# SparkFun_Thing_Plus_NINA-B306.net
KiCad netlist of a schematic drawn in EAGLE
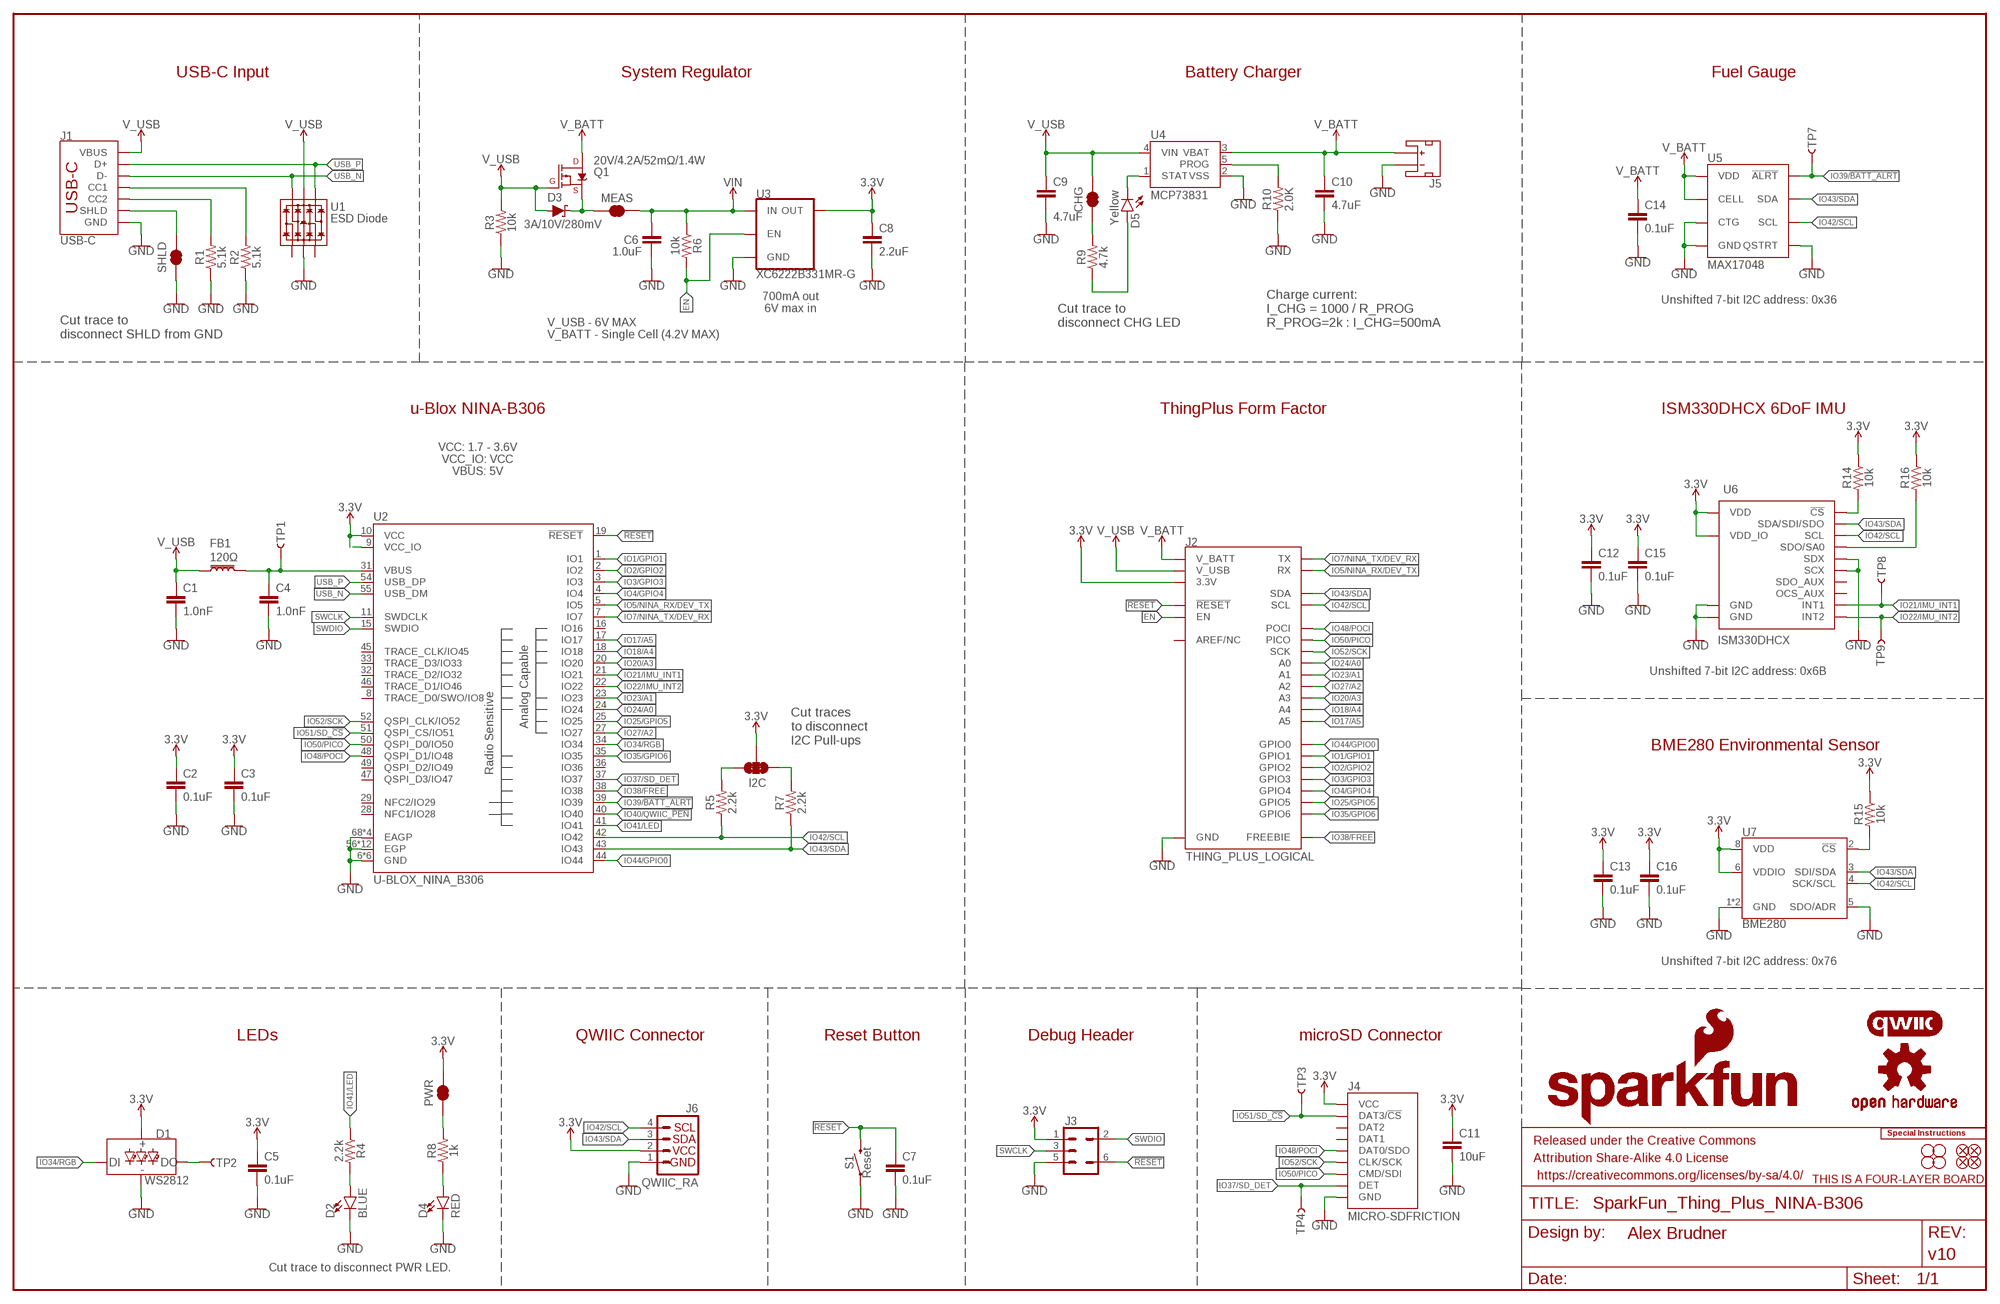
[diagram p0: schematic, sheet 1]

(export (version "E")
  (design (tool "Eeschema 10.0.6"))
  (components
    (comp (ref "C1")
      (value "1.0nF")
      (footprint "eagle-import:0402-TIGHT")
      (libsource (lib "eagle-import") (part "1.0NF/1000PF-0402_TIGHT-50V-10%"))
    )
    (comp (ref "C2")
      (value "0.1uF")
      (footprint "eagle-import:0402-TIGHT")
      (libsource (lib "eagle-import") (part "0.1UF-0402T-6.3V-10%-X7R"))
    )
    (comp (ref "C3")
      (value "0.1uF")
      (footprint "eagle-import:0402-TIGHT")
      (libsource (lib "eagle-import") (part "0.1UF-0402T-6.3V-10%-X7R"))
    )
    (comp (ref "C4")
      (value "1.0nF")
      (footprint "eagle-import:0402-TIGHT")
      (libsource (lib "eagle-import") (part "1.0NF/1000PF-0402_TIGHT-50V-10%"))
    )
    (comp (ref "C5")
      (value "0.1uF")
      (footprint "eagle-import:0402-TIGHT")
      (libsource (lib "eagle-import") (part "0.1UF-0402T-6.3V-10%-X7R"))
    )
    (comp (ref "C6")
      (value "1.0uF")
      (footprint "eagle-import:0402-TIGHT")
      (libsource (lib "eagle-import") (part "1.0UF-0402T-16V-10%"))
    )
    (comp (ref "C7")
      (value "0.1uF")
      (footprint "eagle-import:0402-TIGHT")
      (libsource (lib "eagle-import") (part "0.1UF-0402T-10V-10%-X7R"))
    )
    (comp (ref "C8")
      (value "2.2uF")
      (footprint "eagle-import:0402-TIGHT")
      (libsource (lib "eagle-import") (part "2.2UF-0402_TIGHT-10V-10%-X5R"))
    )
    (comp (ref "C9")
      (value "4.7uF")
      (footprint "eagle-import:0402-TIGHT")
      (libsource (lib "eagle-import") (part "4.7UF-0402_TIGHT-6.3V-20%-X5R"))
    )
    (comp (ref "C10")
      (value "4.7uF")
      (footprint "eagle-import:0402-TIGHT")
      (libsource (lib "eagle-import") (part "4.7UF-0402_TIGHT-6.3V-20%-X5R"))
    )
    (comp (ref "C11")
      (value "10uF")
      (footprint "eagle-import:0402-TIGHT")
      (libsource (lib "eagle-import") (part "10UF-0402T-6.3V-20%"))
    )
    (comp (ref "C12")
      (value "0.1uF")
      (footprint "eagle-import:0402-TIGHT")
      (libsource (lib "eagle-import") (part "0.1UF-0402T-6.3V-10%-X7R"))
    )
    (comp (ref "C13")
      (value "0.1uF")
      (footprint "eagle-import:0402-TIGHT")
      (libsource (lib "eagle-import") (part "0.1UF-0402T-6.3V-10%-X7R"))
    )
    (comp (ref "C14")
      (value "0.1uF")
      (footprint "eagle-import:0402-TIGHT")
      (libsource (lib "eagle-import") (part "0.1UF-0402T-10V-10%-X7R"))
    )
    (comp (ref "C15")
      (value "0.1uF")
      (footprint "eagle-import:0402-TIGHT")
      (libsource (lib "eagle-import") (part "0.1UF-0402T-6.3V-10%-X7R"))
    )
    (comp (ref "C16")
      (value "0.1uF")
      (footprint "eagle-import:0402-TIGHT")
      (libsource (lib "eagle-import") (part "0.1UF-0402T-6.3V-10%-X7R"))
    )
    (comp (ref "CHG")
      (value "JUMPER-SMT_2_NC_TRACE_SILK")
      (footprint "eagle-import:SMT-JUMPER_2_NC_TRACE_SILK")
      (libsource (lib "eagle-import") (part "JUMPER-SMT_2_NC_TRACE_SILK"))
    )
    (comp (ref "D1")
      (value "WS2812")
      (footprint "eagle-import:WS2812-2020")
      (libsource (lib "eagle-import") (part "WS2812_2020"))
    )
    (comp (ref "D2")
      (value "BLUE")
      (footprint "eagle-import:LED-0603")
      (libsource (lib "eagle-import") (part "LED-BLUE0603"))
    )
    (comp (ref "D3")
      (value "3A/10V/280mV")
      (footprint "eagle-import:SOD-323")
      (libsource (lib "eagle-import") (part "DIODE-SCHOTTKY-BAT60A"))
    )
    (comp (ref "D4")
      (value "RED")
      (footprint "eagle-import:LED-0603")
      (libsource (lib "eagle-import") (part "LED-RED0603"))
    )
    (comp (ref "D5")
      (value "Yellow")
      (footprint "eagle-import:LED-0603")
      (libsource (lib "eagle-import") (part "LED-YELLOW0603"))
    )
    (comp (ref "FB1")
      (value "120Ω")
      (footprint "eagle-import:0402")
      (fields (field (name "MFG_PART") "BLM15HB121SN1D"))
      (libsource (lib "eagle-import") (part "FERRITE_BEAD-120_OHM-0402"))
    )
    (comp (ref "FD1")
      (value "FIDUCIALUFIDUCIAL")
      (footprint "eagle-import:FIDUCIAL-MICRO")
      (libsource (lib "eagle-import") (part "FIDUCIALUFIDUCIAL"))
    )
    (comp (ref "FD2")
      (value "FIDUCIALUFIDUCIAL")
      (footprint "eagle-import:FIDUCIAL-MICRO")
      (libsource (lib "eagle-import") (part "FIDUCIALUFIDUCIAL"))
    )
    (comp (ref "FD3")
      (value "FIDUCIALUFIDUCIAL")
      (footprint "eagle-import:FIDUCIAL-MICRO")
      (libsource (lib "eagle-import") (part "FIDUCIALUFIDUCIAL"))
    )
    (comp (ref "FD4")
      (value "FIDUCIALUFIDUCIAL")
      (footprint "eagle-import:FIDUCIAL-MICRO")
      (libsource (lib "eagle-import") (part "FIDUCIALUFIDUCIAL"))
    )
    (comp (ref "FRAME1")
      (value "FRAME-LEDGER")
      (footprint "eagle-import:CREATIVE_COMMONS")
      (fields (field (name "DESIGNER") "Alex Brudner") (field (name "REV") "v10"))
      (libsource (lib "eagle-import") (part "FRAME-LEDGER"))
    )
    (comp (ref "H1")
      (value "STAND-OFFTIGHT")
      (footprint "eagle-import:STAND-OFF-TIGHT")
      (libsource (lib "eagle-import") (part "STAND-OFFTIGHT"))
    )
    (comp (ref "H2")
      (value "STAND-OFFTIGHT")
      (footprint "eagle-import:STAND-OFF-TIGHT")
      (libsource (lib "eagle-import") (part "STAND-OFFTIGHT"))
    )
    (comp (ref "H3")
      (value "STAND-OFFTIGHT")
      (footprint "eagle-import:STAND-OFF-TIGHT")
      (libsource (lib "eagle-import") (part "STAND-OFFTIGHT"))
    )
    (comp (ref "H4")
      (value "STAND-OFFTIGHT")
      (footprint "eagle-import:STAND-OFF-TIGHT")
      (libsource (lib "eagle-import") (part "STAND-OFFTIGHT"))
    )
    (comp (ref "I2C")
      (value "JUMPER-SMT_3_2-NC_TRACE_SILK")
      (footprint "eagle-import:SMT-JUMPER_3_2-NC_TRACE_SILK")
      (libsource (lib "eagle-import") (part "JUMPER-SMT_3_2-NC_TRACE_SILK"))
    )
    (comp (ref "J1")
      (value "USB-C")
      (footprint "eagle-import:USB-C-16P-4LAYER-ISOLATED")
      (libsource (lib "eagle-import") (part "USB_C_4-LAYER-ISOLATED"))
    )
    (comp (ref "J2")
      (value "THING_PLUS_LOGICAL")
      (footprint "eagle-import:THING_PLUS")
      (libsource (lib "eagle-import") (part "THING_PLUS_LOGICAL"))
    )
    (comp (ref "J3")
      (value "CONN_03X2_NO4")
      (footprint "eagle-import:PAD_05_03X2_TP_NO4")
      (libsource (lib "eagle-import") (part "CONN_03X2_NO4"))
    )
    (comp (ref "J4")
      (value "MICRO-SDFRICTION")
      (footprint "eagle-import:MICROSD_TINY")
      (libsource (lib "eagle-import") (part "MICRO-SDFRICTION"))
    )
    (comp (ref "J5")
      (value "JST_2MM_MALE")
      (footprint "eagle-import:JST-2-SMD")
      (libsource (lib "eagle-import") (part "JST_2MM_MALE"))
    )
    (comp (ref "J6")
      (value "QWIIC_RA")
      (footprint "eagle-import:JST04_1MM_RA")
      (libsource (lib "eagle-import") (part "QWIIC_CONNECTORJS-1MM"))
    )
    (comp (ref "LOGO1")
      (value "SFE_LOGO_NAME_FLAME.1_INCH")
      (footprint "eagle-import:SFE_LOGO_NAME_FLAME_.1")
      (libsource (lib "eagle-import") (part "SFE_LOGO_NAME_FLAME.1_INCH"))
    )
    (comp (ref "LOGO2")
      (value "FOUR_LAYER_WARNING")
      (footprint "eagle-import:FOUR_LAYER_WARNING")
      (libsource (lib "eagle-import") (part "FOUR_LAYER_WARNING"))
    )
    (comp (ref "LOGO3")
      (value "SPECIAL_INSTRUCTIONS-ORDERING")
      (footprint "eagle-import:ORDERING_INSTRUCTIONS")
      (libsource (lib "eagle-import") (part "SPECIAL_INSTRUCTIONS-ORDERING"))
    )
    (comp (ref "LOGO4")
      (value "QWIIC_LOGO_4MM")
      (footprint "eagle-import:QWIIC_4MM")
      (libsource (lib "eagle-import") (part "QWIIC_LOGO_4MM"))
    )
    (comp (ref "LOGO5")
      (value "OSHW-LOGOMINI")
      (footprint "eagle-import:OSHW-LOGO-MINI")
      (libsource (lib "eagle-import") (part "OSHW-LOGOMINI"))
    )
    (comp (ref "MEAS")
      (value "JUMPER-COMBO_2_NC_TRACE")
      (footprint "eagle-import:COMBO-JUMPER_2_NC_TRACE")
      (libsource (lib "eagle-import") (part "JUMPER-COMBO_2_NC_TRACE"))
    )
    (comp (ref "PWR")
      (value "JUMPER-SMT_2_NC_TRACE_SILK")
      (footprint "eagle-import:SMT-JUMPER_2_NC_TRACE_SILK")
      (libsource (lib "eagle-import") (part "JUMPER-SMT_2_NC_TRACE_SILK"))
    )
    (comp (ref "Q1")
      (value "20V/4.2A/52mΩ/1.4W")
      (footprint "eagle-import:SOT23-3")
      (libsource (lib "eagle-import") (part "MOSFET_PCH-DMG2305UX-7"))
    )
    (comp (ref "R1")
      (value "5.1k")
      (footprint "eagle-import:0402-TIGHT")
      (libsource (lib "eagle-import") (part "5.1KOHM-0402T-1/16W-1%"))
    )
    (comp (ref "R2")
      (value "5.1k")
      (footprint "eagle-import:0402-TIGHT")
      (libsource (lib "eagle-import") (part "5.1KOHM-0402T-1/16W-1%"))
    )
    (comp (ref "R3")
      (value "10k")
      (footprint "eagle-import:0402-TIGHT")
      (libsource (lib "eagle-import") (part "10KOHM-0402T-1/16W-1%"))
    )
    (comp (ref "R4")
      (value "2.2k")
      (footprint "eagle-import:0402-TIGHT")
      (libsource (lib "eagle-import") (part "2.2KOHM-0402T-1/16W-1%"))
    )
    (comp (ref "R5")
      (value "2.2k")
      (footprint "eagle-import:0402-TIGHT")
      (libsource (lib "eagle-import") (part "2.2KOHM-0402T-1/16W-1%"))
    )
    (comp (ref "R6")
      (value "10k")
      (footprint "eagle-import:0402-TIGHT")
      (libsource (lib "eagle-import") (part "10KOHM-0402T-1/16W-1%"))
    )
    (comp (ref "R7")
      (value "2.2k")
      (footprint "eagle-import:0402-TIGHT")
      (libsource (lib "eagle-import") (part "2.2KOHM-0402T-1/16W-1%"))
    )
    (comp (ref "R8")
      (value "1k")
      (footprint "eagle-import:0402-TIGHT")
      (libsource (lib "eagle-import") (part "1KOHM-0402T-1/16W-1%"))
    )
    (comp (ref "R9")
      (value "4.7k")
      (footprint "eagle-import:0402-TIGHT")
      (libsource (lib "eagle-import") (part "4.7KOHM-0402T-1/16W-1%"))
    )
    (comp (ref "R10")
      (value "2.0K")
      (footprint "eagle-import:0402-TIGHT")
      (libsource (lib "eagle-import") (part "2.0KOHM-0402T-1/16W-1%"))
    )
    (comp (ref "R14")
      (value "10k")
      (footprint "eagle-import:0402-TIGHT")
      (libsource (lib "eagle-import") (part "10KOHM-0402T-1/16W-1%"))
    )
    (comp (ref "R15")
      (value "10k")
      (footprint "eagle-import:0402-TIGHT")
      (libsource (lib "eagle-import") (part "10KOHM-0402T-1/16W-1%"))
    )
    (comp (ref "R16")
      (value "10k")
      (footprint "eagle-import:0402-TIGHT")
      (libsource (lib "eagle-import") (part "10KOHM-0402T-1/16W-1%"))
    )
    (comp (ref "S1")
      (value "Reset")
      (footprint "eagle-import:TACTILE_SWITCH_SMD_4.6X2.8MM")
      (libsource (lib "eagle-import") (part "MOMENTARY-SWITCH-SPST-SMD-4.6X2.8MM"))
    )
    (comp (ref "SHLD")
      (value "JUMPER-SMT_2_NC_TRACE_SILK")
      (footprint "eagle-import:SMT-JUMPER_2_NC_TRACE_SILK")
      (libsource (lib "eagle-import") (part "JUMPER-SMT_2_NC_TRACE_SILK"))
    )
    (comp (ref "TP1")
      (value "TEST-POINT3X5")
      (footprint "eagle-import:PAD.03X.05")
      (libsource (lib "eagle-import") (part "TEST-POINT3X5"))
    )
    (comp (ref "TP2")
      (value "TEST-POINT3X5")
      (footprint "eagle-import:PAD.03X.05")
      (libsource (lib "eagle-import") (part "TEST-POINT3X5"))
    )
    (comp (ref "TP3")
      (value "TEST-POINT3X5")
      (footprint "eagle-import:PAD.03X.05")
      (libsource (lib "eagle-import") (part "TEST-POINT3X5"))
    )
    (comp (ref "TP4")
      (value "TEST-POINT3X5")
      (footprint "eagle-import:PAD.03X.05")
      (libsource (lib "eagle-import") (part "TEST-POINT3X5"))
    )
    (comp (ref "TP7")
      (value "TEST-POINT3X5")
      (footprint "eagle-import:PAD.03X.05")
      (libsource (lib "eagle-import") (part "TEST-POINT3X5"))
    )
    (comp (ref "TP8")
      (value "TEST-POINT3X5")
      (footprint "eagle-import:PAD.03X.05")
      (libsource (lib "eagle-import") (part "TEST-POINT3X5"))
    )
    (comp (ref "TP9")
      (value "TEST-POINT3X5")
      (footprint "eagle-import:PAD.03X.05")
      (libsource (lib "eagle-import") (part "TEST-POINT3X5"))
    )
    (comp (ref "U1")
      (value "ESD Diode")
      (footprint "eagle-import:SOT-23-6")
      (libsource (lib "eagle-import") (part "TVS_DIODE_ARRAY_DT1042-04SO-7"))
    )
    (comp (ref "U2")
      (value "U-BLOX_NINA_B306")
      (footprint "eagle-import:NINA_B306")
      (libsource (lib "eagle-import") (part "U-BLOX_NINA_B306"))
    )
    (comp (ref "U3")
      (value "XC6222B331MR-G")
      (footprint "eagle-import:SOT23-5")
      (libsource (lib "eagle-import") (part "XC6222B331MR-G"))
    )
    (comp (ref "U4")
      (value "MCP73831")
      (footprint "eagle-import:SOT23-5")
      (libsource (lib "eagle-import") (part "MCP73831"))
    )
    (comp (ref "U5")
      (value "MAX17048")
      (footprint "eagle-import:DFN-8")
      (libsource (lib "eagle-import") (part "MAX17048DFN8"))
    )
    (comp (ref "U6")
      (value "ISM330DHCX")
      (footprint "eagle-import:LGA-14L")
      (libsource (lib "eagle-import") (part "ISM330DHCX"))
    )
    (comp (ref "U7")
      (value "BME280")
      (footprint "eagle-import:LGA-8-2.5X2.5")
      (libsource (lib "eagle-import") (part "BME280"))
    )
  )
  (nets
    (net (code "1") (name "/IO39{slash}~{BATT_ALRT}") (class "Default")
      (node (ref "TP7") (pin "1") (pinfunction "1_1") (pintype "bidirectional"))
      (node (ref "U2") (pin "39") (pinfunction "IO39_39") (pintype "bidirectional"))
      (node (ref "U5") (pin "5") (pinfunction "~{ALRT}_5") (pintype "bidirectional"))
    )
    (net (code "2") (name "/IO40{slash}QWIIC_~{PEN}") (class "Default")
      (node (ref "U2") (pin "40") (pinfunction "IO40_40") (pintype "bidirectional"))
    )
    (net (code "3") (name "/IO51{slash}SD_~{CS}") (class "Default")
      (node (ref "J4") (pin "2") (pinfunction "DAT3/~{CS}_2") (pintype "bidirectional"))
      (node (ref "TP3") (pin "1") (pinfunction "1_1") (pintype "bidirectional"))
      (node (ref "U2") (pin "51") (pinfunction "QSPI_CS/IO51_51") (pintype "bidirectional"))
    )
    (net (code "4") (name "/~{RESET}") (class "Default")
      (node (ref "C7") (pin "1") (pinfunction "1_1") (pintype "passive"))
      (node (ref "J2") (pin "28") (pinfunction "~{RESET}_28") (pintype "bidirectional"))
      (node (ref "J3") (pin "6") (pinfunction "6_6") (pintype "bidirectional"))
      (node (ref "S1") (pin "3") (pinfunction "2_3") (pintype "passive"))
      (node (ref "S1") (pin "4") (pinfunction "2_4") (pintype "passive"))
      (node (ref "U2") (pin "19") (pinfunction "~{RESET}_19") (pintype "input"))
    )
    (net (code "5") (name "3.3V") (class "Default")
      (node (ref "C11") (pin "1") (pinfunction "1_1") (pintype "passive"))
      (node (ref "C12") (pin "1") (pinfunction "1_1") (pintype "passive"))
      (node (ref "C13") (pin "1") (pinfunction "1_1") (pintype "passive"))
      (node (ref "C15") (pin "1") (pinfunction "1_1") (pintype "passive"))
      (node (ref "C16") (pin "1") (pinfunction "1_1") (pintype "passive"))
      (node (ref "C2") (pin "1") (pinfunction "1_1") (pintype "passive"))
      (node (ref "C3") (pin "1") (pinfunction "1_1") (pintype "passive"))
      (node (ref "C5") (pin "1") (pinfunction "1_1") (pintype "passive"))
      (node (ref "C8") (pin "1") (pinfunction "1_1") (pintype "passive"))
      (node (ref "D1") (pin "VCC") (pinfunction "VCC_VCC") (pintype "bidirectional"))
      (node (ref "I2C") (pin "2") (pinfunction "2_2") (pintype "passive"))
      (node (ref "J2") (pin "27") (pinfunction "3.3V_27") (pintype "bidirectional"))
      (node (ref "J3") (pin "1") (pinfunction "1_1") (pintype "bidirectional"))
      (node (ref "J4") (pin "4") (pinfunction "VCC_4") (pintype "bidirectional"))
      (node (ref "J6") (pin "2") (pinfunction "2_2") (pintype "power_in"))
      (node (ref "PWR") (pin "2") (pinfunction "2_2") (pintype "passive"))
      (node (ref "R14") (pin "1") (pinfunction "1_1") (pintype "passive"))
      (node (ref "R15") (pin "1") (pinfunction "1_1") (pintype "passive"))
      (node (ref "R16") (pin "1") (pinfunction "1_1") (pintype "passive"))
      (node (ref "U2") (pin "10") (pinfunction "VCC_10") (pintype "power_in"))
      (node (ref "U2") (pin "9") (pinfunction "VCC_IO_9") (pintype "power_in"))
      (node (ref "U3") (pin "5") (pinfunction "OUT_5") (pintype "passive"))
      (node (ref "U6") (pin "P5") (pinfunction "VDD_IO_P5") (pintype "power_in"))
      (node (ref "U6") (pin "P8") (pinfunction "VDD_P8") (pintype "power_in"))
      (node (ref "U7") (pin "6") (pinfunction "VDDIO_6") (pintype "bidirectional"))
      (node (ref "U7") (pin "8") (pinfunction "VDD_8") (pintype "bidirectional"))
    )
    (net (code "6") (name "EN") (class "Default")
      (node (ref "J2") (pin "11") (pinfunction "EN_11") (pintype "bidirectional"))
      (node (ref "R6") (pin "2") (pinfunction "2_2") (pintype "passive"))
      (node (ref "U3") (pin "3") (pinfunction "EN_3") (pintype "input"))
    )
    (net (code "7") (name "GND") (class "Default")
      (node (ref "C1") (pin "2") (pinfunction "2_2") (pintype "passive"))
      (node (ref "C10") (pin "2") (pinfunction "2_2") (pintype "passive"))
      (node (ref "C11") (pin "2") (pinfunction "2_2") (pintype "passive"))
      (node (ref "C12") (pin "2") (pinfunction "2_2") (pintype "passive"))
      (node (ref "C13") (pin "2") (pinfunction "2_2") (pintype "passive"))
      (node (ref "C14") (pin "2") (pinfunction "2_2") (pintype "passive"))
      (node (ref "C15") (pin "2") (pinfunction "2_2") (pintype "passive"))
      (node (ref "C16") (pin "2") (pinfunction "2_2") (pintype "passive"))
      (node (ref "C2") (pin "2") (pinfunction "2_2") (pintype "passive"))
      (node (ref "C3") (pin "2") (pinfunction "2_2") (pintype "passive"))
      (node (ref "C4") (pin "2") (pinfunction "2_2") (pintype "passive"))
      (node (ref "C5") (pin "2") (pinfunction "2_2") (pintype "passive"))
      (node (ref "C6") (pin "2") (pinfunction "2_2") (pintype "passive"))
      (node (ref "C7") (pin "2") (pinfunction "2_2") (pintype "passive"))
      (node (ref "C8") (pin "2") (pinfunction "2_2") (pintype "passive"))
      (node (ref "C9") (pin "2") (pinfunction "2_2") (pintype "passive"))
      (node (ref "D1") (pin "GND") (pinfunction "GND_GND") (pintype "bidirectional"))
      (node (ref "D2") (pin "C") (pinfunction "C_C") (pintype "passive"))
      (node (ref "D4") (pin "C") (pinfunction "C_C") (pintype "passive"))
      (node (ref "J1") (pin "GND") (pinfunction "GND_GND") (pintype "bidirectional"))
      (node (ref "J1") (pin "GND2") (pinfunction "GND_GND2") (pintype "bidirectional"))
      (node (ref "J2") (pin "25") (pinfunction "GND_25") (pintype "bidirectional"))
      (node (ref "J3") (pin "5") (pinfunction "5_5") (pintype "bidirectional"))
      (node (ref "J4") (pin "6") (pinfunction "GND_6") (pintype "bidirectional"))
      (node (ref "J4") (pin "GND1") (pinfunction "GND_GND1") (pintype "bidirectional"))
      (node (ref "J4") (pin "GND2") (pinfunction "GND_GND2") (pintype "bidirectional"))
      (node (ref "J4") (pin "GND3") (pinfunction "GND_GND3") (pintype "bidirectional"))
      (node (ref "J4") (pin "GND4") (pinfunction "GND_GND4") (pintype "bidirectional"))
      (node (ref "J4") (pin "GND5") (pinfunction "GND_GND5") (pintype "bidirectional"))
      (node (ref "J4") (pin "GND6") (pinfunction "GND_GND6") (pintype "bidirectional"))
      (node (ref "J5") (pin "1") (pinfunction "-_1") (pintype "bidirectional"))
      (node (ref "J6") (pin "1") (pinfunction "1_1") (pintype "power_in"))
      (node (ref "R1") (pin "1") (pinfunction "1_1") (pintype "passive"))
      (node (ref "R10") (pin "1") (pinfunction "1_1") (pintype "passive"))
      (node (ref "R2") (pin "1") (pinfunction "1_1") (pintype "passive"))
      (node (ref "R3") (pin "1") (pinfunction "1_1") (pintype "passive"))
      (node (ref "S1") (pin "1") (pinfunction "1_1") (pintype "passive"))
      (node (ref "S1") (pin "2") (pinfunction "1_2") (pintype "passive"))
      (node (ref "SHLD") (pin "1") (pinfunction "1_1") (pintype "passive"))
      (node (ref "U1") (pin "2") (pinfunction "VSS_2") (pintype "bidirectional"))
      (node (ref "U2") (pin "12") (pinfunction "GND_12") (pintype "power_in"))
      (node (ref "U2") (pin "14") (pinfunction "GND_14") (pintype "power_in"))
      (node (ref "U2") (pin "26") (pinfunction "GND_26") (pintype "power_in"))
      (node (ref "U2") (pin "30") (pinfunction "GND_30") (pintype "power_in"))
      (node (ref "U2") (pin "53") (pinfunction "GND_53") (pintype "power_in"))
      (node (ref "U2") (pin "56") (pinfunction "EGP_56") (pintype "power_in"))
      (node (ref "U2") (pin "57") (pinfunction "EGP_57") (pintype "power_in"))
      (node (ref "U2") (pin "58") (pinfunction "EGP_58") (pintype "power_in"))
      (node (ref "U2") (pin "59") (pinfunction "EGP_59") (pintype "power_in"))
      (node (ref "U2") (pin "6") (pinfunction "GND_6") (pintype "power_in"))
      (node (ref "U2") (pin "60") (pinfunction "EGP_60") (pintype "power_in"))
      (node (ref "U2") (pin "61") (pinfunction "EGP_61") (pintype "power_in"))
      (node (ref "U2") (pin "62") (pinfunction "EGP_62") (pintype "power_in"))
      (node (ref "U2") (pin "63") (pinfunction "EGP_63") (pintype "power_in"))
      (node (ref "U2") (pin "64") (pinfunction "EGP_64") (pintype "power_in"))
      (node (ref "U2") (pin "65") (pinfunction "EGP_65") (pintype "power_in"))
      (node (ref "U2") (pin "66") (pinfunction "EGP_66") (pintype "power_in"))
      (node (ref "U2") (pin "67") (pinfunction "EGP_67") (pintype "power_in"))
      (node (ref "U2") (pin "68") (pinfunction "EAGP_68") (pintype "power_in"))
      (node (ref "U2") (pin "69") (pinfunction "EAGP_69") (pintype "power_in"))
      (node (ref "U2") (pin "70") (pinfunction "EAGP_70") (pintype "power_in"))
      (node (ref "U2") (pin "71") (pinfunction "EAGP_71") (pintype "power_in"))
      (node (ref "U3") (pin "2") (pinfunction "GND_2") (pintype "input"))
      (node (ref "U4") (pin "2") (pinfunction "VSS_2") (pintype "power_in"))
      (node (ref "U5") (pin "1") (pinfunction "CTG_1") (pintype "input"))
      (node (ref "U5") (pin "4") (pinfunction "GND_4") (pintype "bidirectional"))
      (node (ref "U5") (pin "6") (pinfunction "QSTRT_6") (pintype "bidirectional"))
      (node (ref "U5") (pin "9") (pinfunction "GND_9") (pintype "bidirectional"))
      (node (ref "U6") (pin "P2") (pinfunction "SDX_P2") (pintype "bidirectional"))
      (node (ref "U6") (pin "P3") (pinfunction "SCX_P3") (pintype "bidirectional"))
      (node (ref "U6") (pin "P6") (pinfunction "GND_P6") (pintype "power_in"))
      (node (ref "U6") (pin "P7") (pinfunction "GND_P7") (pintype "power_in"))
      (node (ref "U7") (pin "1") (pinfunction "GND_1") (pintype "bidirectional"))
      (node (ref "U7") (pin "5") (pinfunction "SDO/ADR_5") (pintype "bidirectional"))
      (node (ref "U7") (pin "7") (pinfunction "GND_7") (pintype "bidirectional"))
    )
    (net (code "8") (name "IO1{slash}GPIO1") (class "Default")
      (node (ref "J2") (pin "8") (pinfunction "GPIO1_8") (pintype "bidirectional"))
      (node (ref "U2") (pin "1") (pinfunction "IO1_1") (pintype "bidirectional"))
    )
    (net (code "9") (name "IO2{slash}GPIO2") (class "Default")
      (node (ref "J2") (pin "7") (pinfunction "GPIO2_7") (pintype "bidirectional"))
      (node (ref "U2") (pin "2") (pinfunction "IO2_2") (pintype "bidirectional"))
    )
    (net (code "10") (name "IO3{slash}GPIO3") (class "Default")
      (node (ref "J2") (pin "6") (pinfunction "GPIO3_6") (pintype "bidirectional"))
      (node (ref "U2") (pin "3") (pinfunction "IO3_3") (pintype "bidirectional"))
    )
    (net (code "11") (name "IO4{slash}GPIO4") (class "Default")
      (node (ref "J2") (pin "5") (pinfunction "GPIO4_5") (pintype "bidirectional"))
      (node (ref "U2") (pin "4") (pinfunction "IO4_4") (pintype "bidirectional"))
    )
    (net (code "12") (name "IO5{slash}NINA_RX{slash}DEV_TX") (class "Default")
      (node (ref "J2") (pin "15") (pinfunction "RX_15") (pintype "bidirectional"))
      (node (ref "U2") (pin "5") (pinfunction "IO5_5") (pintype "bidirectional"))
    )
    (net (code "13") (name "IO7{slash}NINA_TX{slash}DEV_RX") (class "Default")
      (node (ref "J2") (pin "14") (pinfunction "TX_14") (pintype "bidirectional"))
      (node (ref "U2") (pin "7") (pinfunction "IO7_7") (pintype "bidirectional"))
    )
    (net (code "14") (name "IO17{slash}A5") (class "Default")
      (node (ref "J2") (pin "19") (pinfunction "A5_19") (pintype "bidirectional"))
      (node (ref "U2") (pin "17") (pinfunction "IO17_17") (pintype "bidirectional"))
    )
    (net (code "15") (name "IO18{slash}A4") (class "Default")
      (node (ref "J2") (pin "20") (pinfunction "A4_20") (pintype "bidirectional"))
      (node (ref "U2") (pin "18") (pinfunction "IO18_18") (pintype "bidirectional"))
    )
    (net (code "16") (name "IO20{slash}A3") (class "Default")
      (node (ref "J2") (pin "21") (pinfunction "A3_21") (pintype "bidirectional"))
      (node (ref "U2") (pin "20") (pinfunction "IO20_20") (pintype "bidirectional"))
    )
    (net (code "17") (name "IO21{slash}IMU_INT1") (class "Default")
      (node (ref "TP8") (pin "1") (pinfunction "1_1") (pintype "bidirectional"))
      (node (ref "U2") (pin "21") (pinfunction "IO21_21") (pintype "bidirectional"))
      (node (ref "U6") (pin "P4") (pinfunction "INT1_P4") (pintype "bidirectional"))
    )
    (net (code "18") (name "IO22{slash}IMU_INT2") (class "Default")
      (node (ref "TP9") (pin "1") (pinfunction "1_1") (pintype "bidirectional"))
      (node (ref "U2") (pin "22") (pinfunction "IO22_22") (pintype "bidirectional"))
      (node (ref "U6") (pin "P9") (pinfunction "INT2_P9") (pintype "bidirectional"))
    )
    (net (code "19") (name "IO23{slash}A1") (class "Default")
      (node (ref "J2") (pin "23") (pinfunction "A1_23") (pintype "bidirectional"))
      (node (ref "U2") (pin "23") (pinfunction "IO23_23") (pintype "bidirectional"))
    )
    (net (code "20") (name "IO24{slash}A0") (class "Default")
      (node (ref "J2") (pin "24") (pinfunction "A0_24") (pintype "bidirectional"))
      (node (ref "U2") (pin "24") (pinfunction "IO24_24") (pintype "bidirectional"))
    )
    (net (code "21") (name "IO25{slash}GPIO5") (class "Default")
      (node (ref "J2") (pin "4") (pinfunction "GPIO5_4") (pintype "bidirectional"))
      (node (ref "U2") (pin "25") (pinfunction "IO25_25") (pintype "bidirectional"))
    )
    (net (code "22") (name "IO27{slash}A2") (class "Default")
      (node (ref "J2") (pin "22") (pinfunction "A2_22") (pintype "bidirectional"))
      (node (ref "U2") (pin "27") (pinfunction "IO27_27") (pintype "bidirectional"))
    )
    (net (code "23") (name "IO34{slash}RGB") (class "Default")
      (node (ref "D1") (pin "DI") (pinfunction "DI_DI") (pintype "bidirectional"))
      (node (ref "U2") (pin "34") (pinfunction "IO34_34") (pintype "bidirectional"))
    )
    (net (code "24") (name "IO35{slash}GPIO6") (class "Default")
      (node (ref "J2") (pin "3") (pinfunction "GPIO6_3") (pintype "bidirectional"))
      (node (ref "U2") (pin "35") (pinfunction "IO35_35") (pintype "bidirectional"))
    )
    (net (code "25") (name "IO37{slash}SD_DET") (class "Default")
      (node (ref "J4") (pin "9") (pinfunction "DET_9") (pintype "bidirectional"))
      (node (ref "TP4") (pin "1") (pinfunction "1_1") (pintype "bidirectional"))
      (node (ref "U2") (pin "37") (pinfunction "IO37_37") (pintype "bidirectional"))
    )
    (net (code "26") (name "IO38{slash}FREE") (class "Default")
      (node (ref "J2") (pin "13") (pinfunction "FREEBIE_13") (pintype "bidirectional"))
      (node (ref "U2") (pin "38") (pinfunction "IO38_38") (pintype "bidirectional"))
    )
    (net (code "27") (name "IO41{slash}LED") (class "Default")
      (node (ref "R4") (pin "1") (pinfunction "1_1") (pintype "passive"))
      (node (ref "U2") (pin "41") (pinfunction "IO41_41") (pintype "bidirectional"))
    )
    (net (code "28") (name "IO42{slash}SCL") (class "Default")
      (node (ref "J2") (pin "2") (pinfunction "SCL_2") (pintype "bidirectional"))
      (node (ref "J6") (pin "4") (pinfunction "4_4") (pintype "passive"))
      (node (ref "R5") (pin "1") (pinfunction "1_1") (pintype "passive"))
      (node (ref "U2") (pin "42") (pinfunction "IO42_42") (pintype "bidirectional"))
      (node (ref "U5") (pin "7") (pinfunction "SCL_7") (pintype "output"))
      (node (ref "U6") (pin "P13") (pinfunction "SCL_P13") (pintype "bidirectional"))
      (node (ref "U7") (pin "4") (pinfunction "SCK/SCL_4") (pintype "bidirectional"))
    )
    (net (code "29") (name "IO43{slash}SDA") (class "Default")
      (node (ref "J2") (pin "1") (pinfunction "SDA_1") (pintype "bidirectional"))
      (node (ref "J6") (pin "3") (pinfunction "3_3") (pintype "passive"))
      (node (ref "R7") (pin "1") (pinfunction "1_1") (pintype "passive"))
      (node (ref "U2") (pin "43") (pinfunction "IO43_43") (pintype "bidirectional"))
      (node (ref "U5") (pin "8") (pinfunction "SDA_8") (pintype "input"))
      (node (ref "U6") (pin "P14") (pinfunction "SDA/SDI/SDO_P14") (pintype "bidirectional"))
      (node (ref "U7") (pin "3") (pinfunction "SDI/SDA_3") (pintype "bidirectional"))
    )
    (net (code "30") (name "IO44{slash}GPIO0") (class "Default")
      (node (ref "J2") (pin "9") (pinfunction "GPIO0_9") (pintype "bidirectional"))
      (node (ref "U2") (pin "44") (pinfunction "IO44_44") (pintype "bidirectional"))
    )
    (net (code "31") (name "IO48{slash}POCI") (class "Default")
      (node (ref "J2") (pin "16") (pinfunction "POCI_16") (pintype "bidirectional"))
      (node (ref "J4") (pin "7") (pinfunction "DAT0/SDO_7") (pintype "bidirectional"))
      (node (ref "U2") (pin "48") (pinfunction "QSPI_D1/IO48_48") (pintype "bidirectional"))
    )
    (net (code "32") (name "IO50{slash}PICO") (class "Default")
      (node (ref "J2") (pin "17") (pinfunction "PICO_17") (pintype "bidirectional"))
      (node (ref "J4") (pin "3") (pinfunction "CMD/SDI_3") (pintype "bidirectional"))
      (node (ref "U2") (pin "50") (pinfunction "QSPI_D0/IO50_50") (pintype "bidirectional"))
    )
    (net (code "33") (name "IO52{slash}SCK") (class "Default")
      (node (ref "J2") (pin "18") (pinfunction "SCK_18") (pintype "bidirectional"))
      (node (ref "J4") (pin "5") (pinfunction "CLK/SCK_5") (pintype "bidirectional"))
      (node (ref "U2") (pin "52") (pinfunction "QSPI_CLK/IO52_52") (pintype "bidirectional"))
    )
    (net (code "34") (name "Net-(CHG-Pad1)") (class "Default")
      (node (ref "CHG") (pin "1") (pinfunction "1_1") (pintype "passive"))
      (node (ref "R9") (pin "2") (pinfunction "2_2") (pintype "passive"))
    )
    (net (code "35") (name "Net-(D1-PadDO)") (class "Default")
      (node (ref "D1") (pin "DO") (pinfunction "DO_DO") (pintype "bidirectional"))
      (node (ref "TP2") (pin "1") (pinfunction "1_1") (pintype "bidirectional"))
    )
    (net (code "36") (name "Net-(D2-PadA)") (class "Default")
      (node (ref "D2") (pin "A") (pinfunction "A_A") (pintype "passive"))
      (node (ref "R4") (pin "2") (pinfunction "2_2") (pintype "passive"))
    )
    (net (code "37") (name "Net-(D4-PadA)") (class "Default")
      (node (ref "D4") (pin "A") (pinfunction "A_A") (pintype "passive"))
      (node (ref "R8") (pin "1") (pinfunction "1_1") (pintype "passive"))
    )
    (net (code "38") (name "Net-(D5-PadA)") (class "Default")
      (node (ref "D5") (pin "A") (pinfunction "A_A") (pintype "passive"))
      (node (ref "R9") (pin "1") (pinfunction "1_1") (pintype "passive"))
    )
    (net (code "39") (name "Net-(I2C-Pad1)") (class "Default")
      (node (ref "I2C") (pin "1") (pinfunction "1_1") (pintype "passive"))
      (node (ref "R7") (pin "2") (pinfunction "2_2") (pintype "passive"))
    )
    (net (code "40") (name "Net-(I2C-Pad3)") (class "Default")
      (node (ref "I2C") (pin "3") (pinfunction "3_3") (pintype "passive"))
      (node (ref "R5") (pin "2") (pinfunction "2_2") (pintype "passive"))
    )
    (net (code "41") (name "Net-(J1-CC1)") (class "Default")
      (node (ref "J1") (pin "A5") (pinfunction "CC1_A5") (pintype "bidirectional"))
      (node (ref "R2") (pin "2") (pinfunction "2_2") (pintype "passive"))
    )
    (net (code "42") (name "Net-(J1-CC2)") (class "Default")
      (node (ref "J1") (pin "B5") (pinfunction "CC2_B5") (pintype "bidirectional"))
      (node (ref "R1") (pin "2") (pinfunction "2_2") (pintype "passive"))
    )
    (net (code "43") (name "Net-(J1-SHLD-PadSHLD1)") (class "Default")
      (node (ref "J1") (pin "SHLD1") (pinfunction "SHLD_SHLD1") (pintype "bidirectional"))
      (node (ref "J1") (pin "SHLD2") (pinfunction "SHLD_SHLD2") (pintype "bidirectional"))
      (node (ref "J1") (pin "SHLD3") (pinfunction "SHLD_SHLD3") (pintype "bidirectional"))
      (node (ref "J1") (pin "SHLD4") (pinfunction "SHLD_SHLD4") (pintype "bidirectional"))
      (node (ref "J1") (pin "SHLD5") (pinfunction "SHLD_SHLD5") (pintype "bidirectional"))
      (node (ref "J1") (pin "SHLD6") (pinfunction "SHLD_SHLD6") (pintype "bidirectional"))
      (node (ref "J1") (pin "SHLD7") (pinfunction "SHLD_SHLD7") (pintype "bidirectional"))
      (node (ref "J1") (pin "SHLD8") (pinfunction "SHLD_SHLD8") (pintype "bidirectional"))
      (node (ref "SHLD") (pin "2") (pinfunction "2_2") (pintype "passive"))
    )
    (net (code "44") (name "Net-(PWR-Pad1)") (class "Default")
      (node (ref "PWR") (pin "1") (pinfunction "1_1") (pintype "passive"))
      (node (ref "R8") (pin "2") (pinfunction "2_2") (pintype "passive"))
    )
    (net (code "45") (name "Net-(Q1-S)") (class "Default")
      (node (ref "D3") (pin "C") (pinfunction "C_C") (pintype "passive"))
      (node (ref "MEAS") (pin "1") (pinfunction "1_1") (pintype "passive"))
      (node (ref "MEAS") (pin "3") (pinfunction "1_3") (pintype "passive"))
      (node (ref "Q1") (pin "2") (pinfunction "S_2") (pintype "bidirectional"))
    )
    (net (code "46") (name "Net-(U2-VBUS)") (class "Default")
      (node (ref "C4") (pin "1") (pinfunction "1_1") (pintype "passive"))
      (node (ref "FB1") (pin "2") (pinfunction "2_2") (pintype "passive"))
      (node (ref "TP1") (pin "1") (pinfunction "1_1") (pintype "bidirectional"))
      (node (ref "U2") (pin "31") (pinfunction "VBUS_31") (pintype "power_in"))
    )
    (net (code "47") (name "Net-(U4-PROG)") (class "Default")
      (node (ref "R10") (pin "2") (pinfunction "2_2") (pintype "passive"))
      (node (ref "U4") (pin "5") (pinfunction "PROG_5") (pintype "input"))
    )
    (net (code "48") (name "Net-(U4-STAT)") (class "Default")
      (node (ref "D5") (pin "C") (pinfunction "C_C") (pintype "passive"))
      (node (ref "U4") (pin "1") (pinfunction "STAT_1") (pintype "output"))
    )
    (net (code "49") (name "Net-(U6-SDO{slash}SA0)") (class "Default")
      (node (ref "R16") (pin "2") (pinfunction "2_2") (pintype "passive"))
      (node (ref "U6") (pin "P1") (pinfunction "SDO/SA0_P1") (pintype "bidirectional"))
    )
    (net (code "50") (name "Net-(U6-~{CS})") (class "Default")
      (node (ref "R14") (pin "2") (pinfunction "2_2") (pintype "passive"))
      (node (ref "U6") (pin "P12") (pinfunction "~{CS}_P12") (pintype "bidirectional"))
    )
    (net (code "51") (name "Net-(U7-~{CS})") (class "Default")
      (node (ref "R15") (pin "2") (pinfunction "2_2") (pintype "passive"))
      (node (ref "U7") (pin "2") (pinfunction "~{CS}_2") (pintype "bidirectional"))
    )
    (net (code "52") (name "SWCLK") (class "Default")
      (node (ref "J3") (pin "3") (pinfunction "3_3") (pintype "bidirectional"))
      (node (ref "U2") (pin "11") (pinfunction "SWDCLK_11") (pintype "bidirectional"))
    )
    (net (code "53") (name "SWDIO") (class "Default")
      (node (ref "J3") (pin "2") (pinfunction "2_2") (pintype "bidirectional"))
      (node (ref "U2") (pin "15") (pinfunction "SWDIO_15") (pintype "bidirectional"))
    )
    (net (code "54") (name "USB_N") (class "Default")
      (node (ref "J1") (pin "A7") (pinfunction "D-_A7") (pintype "bidirectional"))
      (node (ref "J1") (pin "B7") (pinfunction "D-_B7") (pintype "bidirectional"))
      (node (ref "U1") (pin "6") (pinfunction "IO4_6") (pintype "bidirectional"))
      (node (ref "U2") (pin "55") (pinfunction "USB_DM_55") (pintype "bidirectional"))
    )
    (net (code "55") (name "USB_P") (class "Default")
      (node (ref "J1") (pin "A6") (pinfunction "D+_A6") (pintype "bidirectional"))
      (node (ref "J1") (pin "B6") (pinfunction "D+_B6") (pintype "bidirectional"))
      (node (ref "U1") (pin "4") (pinfunction "IO3_4") (pintype "bidirectional"))
      (node (ref "U2") (pin "54") (pinfunction "USB_DP_54") (pintype "bidirectional"))
    )
    (net (code "56") (name "VIN") (class "Default")
      (node (ref "C6") (pin "1") (pinfunction "1_1") (pintype "passive"))
      (node (ref "MEAS") (pin "2") (pinfunction "2_2") (pintype "passive"))
      (node (ref "MEAS") (pin "4") (pinfunction "2_4") (pintype "passive"))
      (node (ref "R6") (pin "1") (pinfunction "1_1") (pintype "passive"))
      (node (ref "U3") (pin "1") (pinfunction "IN_1") (pintype "input"))
    )
    (net (code "57") (name "V_BATT") (class "Default")
      (node (ref "C10") (pin "1") (pinfunction "1_1") (pintype "passive"))
      (node (ref "C14") (pin "1") (pinfunction "1_1") (pintype "passive"))
      (node (ref "J2") (pin "12") (pinfunction "V_BATT_12") (pintype "bidirectional"))
      (node (ref "J5") (pin "2") (pinfunction "+_2") (pintype "bidirectional"))
      (node (ref "Q1") (pin "3") (pinfunction "D_3") (pintype "bidirectional"))
      (node (ref "U4") (pin "3") (pinfunction "VBAT_3") (pintype "power_in"))
      (node (ref "U5") (pin "2") (pinfunction "CELL_2") (pintype "input"))
      (node (ref "U5") (pin "3") (pinfunction "VDD_3") (pintype "bidirectional"))
    )
    (net (code "58") (name "V_USB") (class "Default")
      (node (ref "C1") (pin "1") (pinfunction "1_1") (pintype "passive"))
      (node (ref "C9") (pin "1") (pinfunction "1_1") (pintype "passive"))
      (node (ref "CHG") (pin "2") (pinfunction "2_2") (pintype "passive"))
      (node (ref "D3") (pin "A") (pinfunction "A_A") (pintype "passive"))
      (node (ref "FB1") (pin "1") (pinfunction "1_1") (pintype "passive"))
      (node (ref "J1") (pin "VBUS1") (pinfunction "VBUS_VBUS1") (pintype "bidirectional"))
      (node (ref "J1") (pin "VBUS2") (pinfunction "VBUS_VBUS2") (pintype "bidirectional"))
      (node (ref "J2") (pin "10") (pinfunction "V_USB_10") (pintype "bidirectional"))
      (node (ref "Q1") (pin "1") (pinfunction "G_1") (pintype "bidirectional"))
      (node (ref "R3") (pin "2") (pinfunction "2_2") (pintype "passive"))
      (node (ref "U1") (pin "5") (pinfunction "VCC_5") (pintype "bidirectional"))
      (node (ref "U4") (pin "4") (pinfunction "VIN_4") (pintype "power_in"))
    )
    (net (code "59") (name "unconnected-(J2-AREF{slash}NC-Pad26)") (class "Default")
      (node (ref "J2") (pin "26") (pinfunction "AREF/NC_26") (pintype "bidirectional"))
    )
    (net (code "60") (name "unconnected-(J4-DAT1-Pad8)") (class "Default")
      (node (ref "J4") (pin "8") (pinfunction "DAT1_8") (pintype "bidirectional"))
    )
    (net (code "61") (name "unconnected-(J4-DAT2-Pad1)") (class "Default")
      (node (ref "J4") (pin "1") (pinfunction "DAT2_1") (pintype "bidirectional"))
    )
    (net (code "62") (name "unconnected-(J5-PAD1-PadNC1)") (class "Default")
      (node (ref "J5") (pin "NC1") (pinfunction "PAD1_NC1") (pintype "bidirectional"))
    )
    (net (code "63") (name "unconnected-(J5-PAD2-PadNC2)") (class "Default")
      (node (ref "J5") (pin "NC2") (pinfunction "PAD2_NC2") (pintype "bidirectional"))
    )
    (net (code "64") (name "unconnected-(U1-IO1-Pad1)") (class "Default")
      (node (ref "U1") (pin "1") (pinfunction "IO1_1") (pintype "bidirectional"))
    )
    (net (code "65") (name "unconnected-(U1-IO2-Pad3)") (class "Default")
      (node (ref "U1") (pin "3") (pinfunction "IO2_3") (pintype "bidirectional"))
    )
    (net (code "66") (name "unconnected-(U2-IO16-Pad16)") (class "Default")
      (node (ref "U2") (pin "16") (pinfunction "IO16_16") (pintype "bidirectional"))
    )
    (net (code "67") (name "unconnected-(U2-IO36-Pad36)") (class "Default")
      (node (ref "U2") (pin "36") (pinfunction "IO36_36") (pintype "bidirectional"))
    )
    (net (code "68") (name "unconnected-(U2-NFC1{slash}IO28-Pad28)") (class "Default")
      (node (ref "U2") (pin "28") (pinfunction "NFC1/IO28_28") (pintype "bidirectional"))
    )
    (net (code "69") (name "unconnected-(U2-NFC2{slash}IO29-Pad29)") (class "Default")
      (node (ref "U2") (pin "29") (pinfunction "NFC2/IO29_29") (pintype "bidirectional"))
    )
    (net (code "70") (name "unconnected-(U2-QSPI_D2{slash}IO49-Pad49)") (class "Default")
      (node (ref "U2") (pin "49") (pinfunction "QSPI_D2/IO49_49") (pintype "bidirectional"))
    )
    (net (code "71") (name "unconnected-(U2-QSPI_D3{slash}IO47-Pad47)") (class "Default")
      (node (ref "U2") (pin "47") (pinfunction "QSPI_D3/IO47_47") (pintype "bidirectional"))
    )
    (net (code "72") (name "unconnected-(U2-TRACE_CLK{slash}IO45-Pad45)") (class "Default")
      (node (ref "U2") (pin "45") (pinfunction "TRACE_CLK/IO45_45") (pintype "bidirectional"))
    )
    (net (code "73") (name "unconnected-(U2-TRACE_D0{slash}SWO{slash}IO8-Pad8)") (class "Default")
      (node (ref "U2") (pin "8") (pinfunction "TRACE_D0/SWO/IO8_8") (pintype "bidirectional"))
    )
    (net (code "74") (name "unconnected-(U2-TRACE_D1{slash}IO46-Pad46)") (class "Default")
      (node (ref "U2") (pin "46") (pinfunction "TRACE_D1/IO46_46") (pintype "bidirectional"))
    )
    (net (code "75") (name "unconnected-(U2-TRACE_D2{slash}IO32-Pad32)") (class "Default")
      (node (ref "U2") (pin "32") (pinfunction "TRACE_D2/IO32_32") (pintype "bidirectional"))
    )
    (net (code "76") (name "unconnected-(U2-TRACE_D3{slash}IO33-Pad33)") (class "Default")
      (node (ref "U2") (pin "33") (pinfunction "TRACE_D3/IO33_33") (pintype "bidirectional"))
    )
    (net (code "77") (name "unconnected-(U6-OCS_AUX-PadP10)") (class "Default")
      (node (ref "U6") (pin "P10") (pinfunction "OCS_AUX_P10") (pintype "bidirectional"))
    )
    (net (code "78") (name "unconnected-(U6-SDO_AUX-PadP11)") (class "Default")
      (node (ref "U6") (pin "P11") (pinfunction "SDO_AUX_P11") (pintype "bidirectional"))
    )
  )
)
